# V1.net
KiCad netlist of a schematic drawn in EAGLE
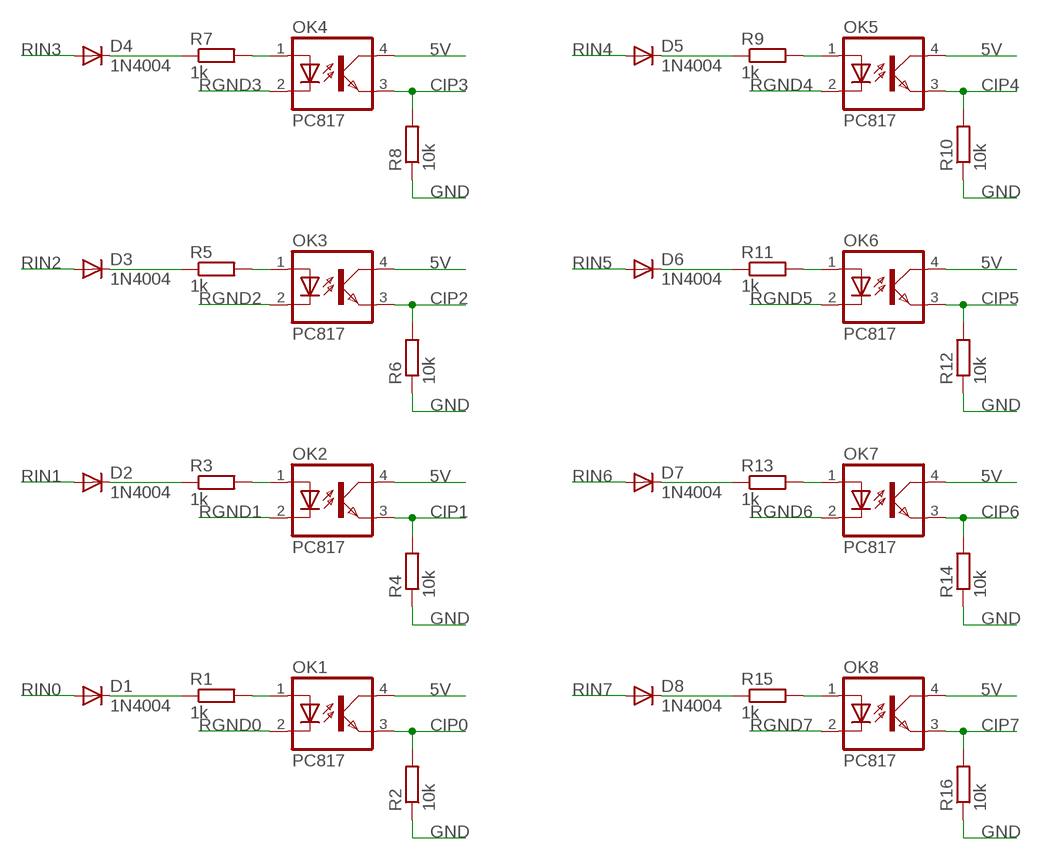
[diagram p0: schematic, sheet 1]
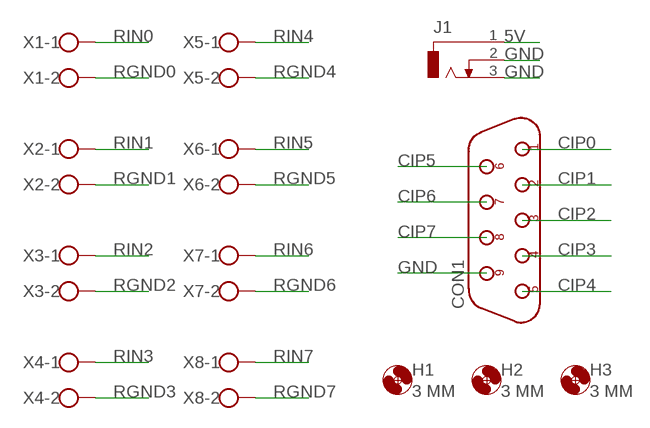
[diagram p1: schematic, sheet 2]

(export (version "E")
  (design (tool "Eeschema 10.0.6"))
  (components
    (comp (ref "D1")
      (value "1N4004")
      (footprint "eagle-import:DO41-10")
      (libsource (lib "eagle-import") (part "1N4004"))
    )
    (comp (ref "D2")
      (value "1N4004")
      (footprint "eagle-import:DO41-10")
      (libsource (lib "eagle-import") (part "1N4004"))
    )
    (comp (ref "D3")
      (value "1N4004")
      (footprint "eagle-import:DO41-10")
      (libsource (lib "eagle-import") (part "1N4004"))
    )
    (comp (ref "D4")
      (value "1N4004")
      (footprint "eagle-import:DO41-10")
      (libsource (lib "eagle-import") (part "1N4004"))
    )
    (comp (ref "D5")
      (value "1N4004")
      (footprint "eagle-import:DO41-10")
      (libsource (lib "eagle-import") (part "1N4004"))
    )
    (comp (ref "D6")
      (value "1N4004")
      (footprint "eagle-import:DO41-10")
      (libsource (lib "eagle-import") (part "1N4004"))
    )
    (comp (ref "D7")
      (value "1N4004")
      (footprint "eagle-import:DO41-10")
      (libsource (lib "eagle-import") (part "1N4004"))
    )
    (comp (ref "D8")
      (value "1N4004")
      (footprint "eagle-import:DO41-10")
      (libsource (lib "eagle-import") (part "1N4004"))
    )
    (comp (ref "OK1")
      (value "PC817")
      (footprint "eagle-import:DIL04")
      (fields (field (name "MPN") "PC817X4J000F"))
      (libsource (lib "eagle-import") (part "PC817"))
    )
    (comp (ref "OK2")
      (value "PC817")
      (footprint "eagle-import:DIL04")
      (fields (field (name "MPN") "PC817X4J000F"))
      (libsource (lib "eagle-import") (part "PC817"))
    )
    (comp (ref "OK3")
      (value "PC817")
      (footprint "eagle-import:DIL04")
      (fields (field (name "MPN") "PC817X4J000F"))
      (libsource (lib "eagle-import") (part "PC817"))
    )
    (comp (ref "OK4")
      (value "PC817")
      (footprint "eagle-import:DIL04")
      (fields (field (name "MPN") "PC817X4J000F"))
      (libsource (lib "eagle-import") (part "PC817"))
    )
    (comp (ref "OK5")
      (value "PC817")
      (footprint "eagle-import:DIL04")
      (fields (field (name "MPN") "PC817X4J000F"))
      (libsource (lib "eagle-import") (part "PC817"))
    )
    (comp (ref "OK6")
      (value "PC817")
      (footprint "eagle-import:DIL04")
      (fields (field (name "MPN") "PC817X4J000F"))
      (libsource (lib "eagle-import") (part "PC817"))
    )
    (comp (ref "OK7")
      (value "PC817")
      (footprint "eagle-import:DIL04")
      (fields (field (name "MPN") "PC817X4J000F"))
      (libsource (lib "eagle-import") (part "PC817"))
    )
    (comp (ref "OK8")
      (value "PC817")
      (footprint "eagle-import:DIL04")
      (fields (field (name "MPN") "PC817X4J000F"))
      (libsource (lib "eagle-import") (part "PC817"))
    )
    (comp (ref "R1")
      (value "1k")
      (footprint "eagle-import:0207_10")
      (libsource (lib "eagle-import") (part "R-EU_0207/10"))
    )
    (comp (ref "R2")
      (value "10k")
      (footprint "eagle-import:0207_10")
      (libsource (lib "eagle-import") (part "R-EU_0207/10"))
    )
    (comp (ref "R3")
      (value "1k")
      (footprint "eagle-import:0207_10")
      (libsource (lib "eagle-import") (part "R-EU_0207/10"))
    )
    (comp (ref "R4")
      (value "10k")
      (footprint "eagle-import:0207_10")
      (libsource (lib "eagle-import") (part "R-EU_0207/10"))
    )
    (comp (ref "R5")
      (value "1k")
      (footprint "eagle-import:0207_10")
      (libsource (lib "eagle-import") (part "R-EU_0207/10"))
    )
    (comp (ref "R6")
      (value "10k")
      (footprint "eagle-import:0207_10")
      (libsource (lib "eagle-import") (part "R-EU_0207/10"))
    )
    (comp (ref "R7")
      (value "1k")
      (footprint "eagle-import:0207_10")
      (libsource (lib "eagle-import") (part "R-EU_0207/10"))
    )
    (comp (ref "R8")
      (value "10k")
      (footprint "eagle-import:0207_10")
      (libsource (lib "eagle-import") (part "R-EU_0207/10"))
    )
    (comp (ref "R9")
      (value "1k")
      (footprint "eagle-import:0207_10")
      (libsource (lib "eagle-import") (part "R-EU_0207/10"))
    )
    (comp (ref "R10")
      (value "10k")
      (footprint "eagle-import:0207_10")
      (libsource (lib "eagle-import") (part "R-EU_0207/10"))
    )
    (comp (ref "R11")
      (value "1k")
      (footprint "eagle-import:0207_10")
      (libsource (lib "eagle-import") (part "R-EU_0207/10"))
    )
    (comp (ref "R12")
      (value "10k")
      (footprint "eagle-import:0207_10")
      (libsource (lib "eagle-import") (part "R-EU_0207/10"))
    )
    (comp (ref "R13")
      (value "1k")
      (footprint "eagle-import:0207_10")
      (libsource (lib "eagle-import") (part "R-EU_0207/10"))
    )
    (comp (ref "R14")
      (value "10k")
      (footprint "eagle-import:0207_10")
      (libsource (lib "eagle-import") (part "R-EU_0207/10"))
    )
    (comp (ref "R15")
      (value "1k")
      (footprint "eagle-import:0207_10")
      (libsource (lib "eagle-import") (part "R-EU_0207/10"))
    )
    (comp (ref "R16")
      (value "10k")
      (footprint "eagle-import:0207_10")
      (libsource (lib "eagle-import") (part "R-EU_0207/10"))
    )
    (comp (ref "CON1")
      (value "DB9F/90")
      (footprint "eagle-import:D-09F_90")
      (libsource (lib "eagle-import") (part "DB9F/90"))
    )
    (comp (ref "H1")
      (value "3 MM")
      (footprint "eagle-import:3,0")
      (libsource (lib "eagle-import") (part "MOUNT-HOLE3.0"))
    )
    (comp (ref "H2")
      (value "3 MM")
      (footprint "eagle-import:3,0")
      (libsource (lib "eagle-import") (part "MOUNT-HOLE3.0"))
    )
    (comp (ref "H3")
      (value "3 MM")
      (footprint "eagle-import:3,0")
      (libsource (lib "eagle-import") (part "MOUNT-HOLE3.0"))
    )
    (comp (ref "J1")
      (value "DCJ0303")
      (footprint "eagle-import:DCJ0303")
      (libsource (lib "eagle-import") (part "DCJ0303"))
    )
    (comp (ref "X1")
      (value "W237-102")
      (footprint "eagle-import:W237-102")
      (fields (field (name "MPN") "237-102"))
      (libsource (lib "eagle-import") (part "W237-102"))
    )
    (comp (ref "X2")
      (value "W237-102")
      (footprint "eagle-import:W237-102")
      (fields (field (name "MPN") "237-102"))
      (libsource (lib "eagle-import") (part "W237-102"))
    )
    (comp (ref "X3")
      (value "W237-102")
      (footprint "eagle-import:W237-102")
      (fields (field (name "MPN") "237-102"))
      (libsource (lib "eagle-import") (part "W237-102"))
    )
    (comp (ref "X4")
      (value "W237-102")
      (footprint "eagle-import:W237-102")
      (fields (field (name "MPN") "237-102"))
      (libsource (lib "eagle-import") (part "W237-102"))
    )
    (comp (ref "X5")
      (value "W237-102")
      (footprint "eagle-import:W237-102")
      (fields (field (name "MPN") "237-102"))
      (libsource (lib "eagle-import") (part "W237-102"))
    )
    (comp (ref "X6")
      (value "W237-102")
      (footprint "eagle-import:W237-102")
      (fields (field (name "MPN") "237-102"))
      (libsource (lib "eagle-import") (part "W237-102"))
    )
    (comp (ref "X7")
      (value "W237-102")
      (footprint "eagle-import:W237-102")
      (fields (field (name "MPN") "237-102"))
      (libsource (lib "eagle-import") (part "W237-102"))
    )
    (comp (ref "X8")
      (value "W237-102")
      (footprint "eagle-import:W237-102")
      (fields (field (name "MPN") "237-102"))
      (libsource (lib "eagle-import") (part "W237-102"))
    )
  )
  (nets
    (net (code "1") (name "5V") (class "Default")
      (node (ref "J1") (pin "1") (pinfunction "1_1") (pintype "passive"))
      (node (ref "OK1") (pin "4") (pinfunction "COL_4") (pintype "passive"))
      (node (ref "OK2") (pin "4") (pinfunction "COL_4") (pintype "passive"))
      (node (ref "OK3") (pin "4") (pinfunction "COL_4") (pintype "passive"))
      (node (ref "OK4") (pin "4") (pinfunction "COL_4") (pintype "passive"))
      (node (ref "OK5") (pin "4") (pinfunction "COL_4") (pintype "passive"))
      (node (ref "OK6") (pin "4") (pinfunction "COL_4") (pintype "passive"))
      (node (ref "OK7") (pin "4") (pinfunction "COL_4") (pintype "passive"))
      (node (ref "OK8") (pin "4") (pinfunction "COL_4") (pintype "passive"))
    )
    (net (code "2") (name "CIP0") (class "Default")
      (node (ref "CON1") (pin "1") (pinfunction "1_1") (pintype "passive"))
      (node (ref "OK1") (pin "3") (pinfunction "EMIT_3") (pintype "passive"))
      (node (ref "R2") (pin "2") (pinfunction "2_2") (pintype "passive"))
    )
    (net (code "3") (name "CIP1") (class "Default")
      (node (ref "CON1") (pin "2") (pinfunction "2_2") (pintype "passive"))
      (node (ref "OK2") (pin "3") (pinfunction "EMIT_3") (pintype "passive"))
      (node (ref "R4") (pin "2") (pinfunction "2_2") (pintype "passive"))
    )
    (net (code "4") (name "CIP2") (class "Default")
      (node (ref "CON1") (pin "3") (pinfunction "3_3") (pintype "passive"))
      (node (ref "OK3") (pin "3") (pinfunction "EMIT_3") (pintype "passive"))
      (node (ref "R6") (pin "2") (pinfunction "2_2") (pintype "passive"))
    )
    (net (code "5") (name "CIP3") (class "Default")
      (node (ref "CON1") (pin "4") (pinfunction "4_4") (pintype "passive"))
      (node (ref "OK4") (pin "3") (pinfunction "EMIT_3") (pintype "passive"))
      (node (ref "R8") (pin "2") (pinfunction "2_2") (pintype "passive"))
    )
    (net (code "6") (name "CIP4") (class "Default")
      (node (ref "CON1") (pin "5") (pinfunction "5_5") (pintype "passive"))
      (node (ref "OK5") (pin "3") (pinfunction "EMIT_3") (pintype "passive"))
      (node (ref "R10") (pin "2") (pinfunction "2_2") (pintype "passive"))
    )
    (net (code "7") (name "CIP5") (class "Default")
      (node (ref "CON1") (pin "6") (pinfunction "6_6") (pintype "passive"))
      (node (ref "OK6") (pin "3") (pinfunction "EMIT_3") (pintype "passive"))
      (node (ref "R12") (pin "2") (pinfunction "2_2") (pintype "passive"))
    )
    (net (code "8") (name "CIP6") (class "Default")
      (node (ref "CON1") (pin "7") (pinfunction "7_7") (pintype "passive"))
      (node (ref "OK7") (pin "3") (pinfunction "EMIT_3") (pintype "passive"))
      (node (ref "R14") (pin "2") (pinfunction "2_2") (pintype "passive"))
    )
    (net (code "9") (name "CIP7") (class "Default")
      (node (ref "CON1") (pin "8") (pinfunction "8_8") (pintype "passive"))
      (node (ref "OK8") (pin "3") (pinfunction "EMIT_3") (pintype "passive"))
      (node (ref "R16") (pin "2") (pinfunction "2_2") (pintype "passive"))
    )
    (net (code "10") (name "GND") (class "Default")
      (node (ref "CON1") (pin "9") (pinfunction "9_9") (pintype "passive"))
      (node (ref "J1") (pin "2") (pinfunction "2_2") (pintype "passive"))
      (node (ref "J1") (pin "3") (pinfunction "3_3") (pintype "passive"))
      (node (ref "R10") (pin "1") (pinfunction "1_1") (pintype "passive"))
      (node (ref "R12") (pin "1") (pinfunction "1_1") (pintype "passive"))
      (node (ref "R14") (pin "1") (pinfunction "1_1") (pintype "passive"))
      (node (ref "R16") (pin "1") (pinfunction "1_1") (pintype "passive"))
      (node (ref "R2") (pin "1") (pinfunction "1_1") (pintype "passive"))
      (node (ref "R4") (pin "1") (pinfunction "1_1") (pintype "passive"))
      (node (ref "R6") (pin "1") (pinfunction "1_1") (pintype "passive"))
      (node (ref "R8") (pin "1") (pinfunction "1_1") (pintype "passive"))
    )
    (net (code "11") (name "Net-(D1-PadC)") (class "Default")
      (node (ref "D1") (pin "C") (pinfunction "C_C") (pintype "passive"))
      (node (ref "R1") (pin "1") (pinfunction "1_1") (pintype "passive"))
    )
    (net (code "12") (name "Net-(D2-PadC)") (class "Default")
      (node (ref "D2") (pin "C") (pinfunction "C_C") (pintype "passive"))
      (node (ref "R3") (pin "1") (pinfunction "1_1") (pintype "passive"))
    )
    (net (code "13") (name "Net-(D3-PadC)") (class "Default")
      (node (ref "D3") (pin "C") (pinfunction "C_C") (pintype "passive"))
      (node (ref "R5") (pin "1") (pinfunction "1_1") (pintype "passive"))
    )
    (net (code "14") (name "Net-(D4-PadC)") (class "Default")
      (node (ref "D4") (pin "C") (pinfunction "C_C") (pintype "passive"))
      (node (ref "R7") (pin "1") (pinfunction "1_1") (pintype "passive"))
    )
    (net (code "15") (name "Net-(D5-PadC)") (class "Default")
      (node (ref "D5") (pin "C") (pinfunction "C_C") (pintype "passive"))
      (node (ref "R9") (pin "1") (pinfunction "1_1") (pintype "passive"))
    )
    (net (code "16") (name "Net-(D6-PadC)") (class "Default")
      (node (ref "D6") (pin "C") (pinfunction "C_C") (pintype "passive"))
      (node (ref "R11") (pin "1") (pinfunction "1_1") (pintype "passive"))
    )
    (net (code "17") (name "Net-(D7-PadC)") (class "Default")
      (node (ref "D7") (pin "C") (pinfunction "C_C") (pintype "passive"))
      (node (ref "R13") (pin "1") (pinfunction "1_1") (pintype "passive"))
    )
    (net (code "18") (name "Net-(D8-PadC)") (class "Default")
      (node (ref "D8") (pin "C") (pinfunction "C_C") (pintype "passive"))
      (node (ref "R15") (pin "1") (pinfunction "1_1") (pintype "passive"))
    )
    (net (code "19") (name "Net-(OK1-A)") (class "Default")
      (node (ref "OK1") (pin "1") (pinfunction "A_1") (pintype "passive"))
      (node (ref "R1") (pin "2") (pinfunction "2_2") (pintype "passive"))
    )
    (net (code "20") (name "Net-(OK2-A)") (class "Default")
      (node (ref "OK2") (pin "1") (pinfunction "A_1") (pintype "passive"))
      (node (ref "R3") (pin "2") (pinfunction "2_2") (pintype "passive"))
    )
    (net (code "21") (name "Net-(OK3-A)") (class "Default")
      (node (ref "OK3") (pin "1") (pinfunction "A_1") (pintype "passive"))
      (node (ref "R5") (pin "2") (pinfunction "2_2") (pintype "passive"))
    )
    (net (code "22") (name "Net-(OK4-A)") (class "Default")
      (node (ref "OK4") (pin "1") (pinfunction "A_1") (pintype "passive"))
      (node (ref "R7") (pin "2") (pinfunction "2_2") (pintype "passive"))
    )
    (net (code "23") (name "Net-(OK5-A)") (class "Default")
      (node (ref "OK5") (pin "1") (pinfunction "A_1") (pintype "passive"))
      (node (ref "R9") (pin "2") (pinfunction "2_2") (pintype "passive"))
    )
    (net (code "24") (name "Net-(OK6-A)") (class "Default")
      (node (ref "OK6") (pin "1") (pinfunction "A_1") (pintype "passive"))
      (node (ref "R11") (pin "2") (pinfunction "2_2") (pintype "passive"))
    )
    (net (code "25") (name "Net-(OK7-A)") (class "Default")
      (node (ref "OK7") (pin "1") (pinfunction "A_1") (pintype "passive"))
      (node (ref "R13") (pin "2") (pinfunction "2_2") (pintype "passive"))
    )
    (net (code "26") (name "Net-(OK8-A)") (class "Default")
      (node (ref "OK8") (pin "1") (pinfunction "A_1") (pintype "passive"))
      (node (ref "R15") (pin "2") (pinfunction "2_2") (pintype "passive"))
    )
    (net (code "27") (name "RGND0") (class "Default")
      (node (ref "OK1") (pin "2") (pinfunction "C_2") (pintype "passive"))
      (node (ref "X1") (pin "2") (pinfunction "KL_2") (pintype "passive"))
    )
    (net (code "28") (name "RGND1") (class "Default")
      (node (ref "OK2") (pin "2") (pinfunction "C_2") (pintype "passive"))
      (node (ref "X2") (pin "2") (pinfunction "KL_2") (pintype "passive"))
    )
    (net (code "29") (name "RGND2") (class "Default")
      (node (ref "OK3") (pin "2") (pinfunction "C_2") (pintype "passive"))
      (node (ref "X3") (pin "2") (pinfunction "KL_2") (pintype "passive"))
    )
    (net (code "30") (name "RGND3") (class "Default")
      (node (ref "OK4") (pin "2") (pinfunction "C_2") (pintype "passive"))
      (node (ref "X4") (pin "2") (pinfunction "KL_2") (pintype "passive"))
    )
    (net (code "31") (name "RGND4") (class "Default")
      (node (ref "OK5") (pin "2") (pinfunction "C_2") (pintype "passive"))
      (node (ref "X5") (pin "2") (pinfunction "KL_2") (pintype "passive"))
    )
    (net (code "32") (name "RGND5") (class "Default")
      (node (ref "OK6") (pin "2") (pinfunction "C_2") (pintype "passive"))
      (node (ref "X6") (pin "2") (pinfunction "KL_2") (pintype "passive"))
    )
    (net (code "33") (name "RGND6") (class "Default")
      (node (ref "OK7") (pin "2") (pinfunction "C_2") (pintype "passive"))
      (node (ref "X7") (pin "2") (pinfunction "KL_2") (pintype "passive"))
    )
    (net (code "34") (name "RGND7") (class "Default")
      (node (ref "OK8") (pin "2") (pinfunction "C_2") (pintype "passive"))
      (node (ref "X8") (pin "2") (pinfunction "KL_2") (pintype "passive"))
    )
    (net (code "35") (name "RIN0") (class "Default")
      (node (ref "D1") (pin "A") (pinfunction "A_A") (pintype "passive"))
      (node (ref "X1") (pin "1") (pinfunction "KL_1") (pintype "passive"))
    )
    (net (code "36") (name "RIN1") (class "Default")
      (node (ref "D2") (pin "A") (pinfunction "A_A") (pintype "passive"))
      (node (ref "X2") (pin "1") (pinfunction "KL_1") (pintype "passive"))
    )
    (net (code "37") (name "RIN2") (class "Default")
      (node (ref "D3") (pin "A") (pinfunction "A_A") (pintype "passive"))
      (node (ref "X3") (pin "1") (pinfunction "KL_1") (pintype "passive"))
    )
    (net (code "38") (name "RIN3") (class "Default")
      (node (ref "D4") (pin "A") (pinfunction "A_A") (pintype "passive"))
      (node (ref "X4") (pin "1") (pinfunction "KL_1") (pintype "passive"))
    )
    (net (code "39") (name "RIN4") (class "Default")
      (node (ref "D5") (pin "A") (pinfunction "A_A") (pintype "passive"))
      (node (ref "X5") (pin "1") (pinfunction "KL_1") (pintype "passive"))
    )
    (net (code "40") (name "RIN5") (class "Default")
      (node (ref "D6") (pin "A") (pinfunction "A_A") (pintype "passive"))
      (node (ref "X6") (pin "1") (pinfunction "KL_1") (pintype "passive"))
    )
    (net (code "41") (name "RIN6") (class "Default")
      (node (ref "D7") (pin "A") (pinfunction "A_A") (pintype "passive"))
      (node (ref "X7") (pin "1") (pinfunction "KL_1") (pintype "passive"))
    )
    (net (code "42") (name "RIN7") (class "Default")
      (node (ref "D8") (pin "A") (pinfunction "A_A") (pintype "passive"))
      (node (ref "X8") (pin "1") (pinfunction "KL_1") (pintype "passive"))
    )
  )
)
